# sticks-apa102-p1b.net
KiCad netlist of a schematic drawn in EAGLE
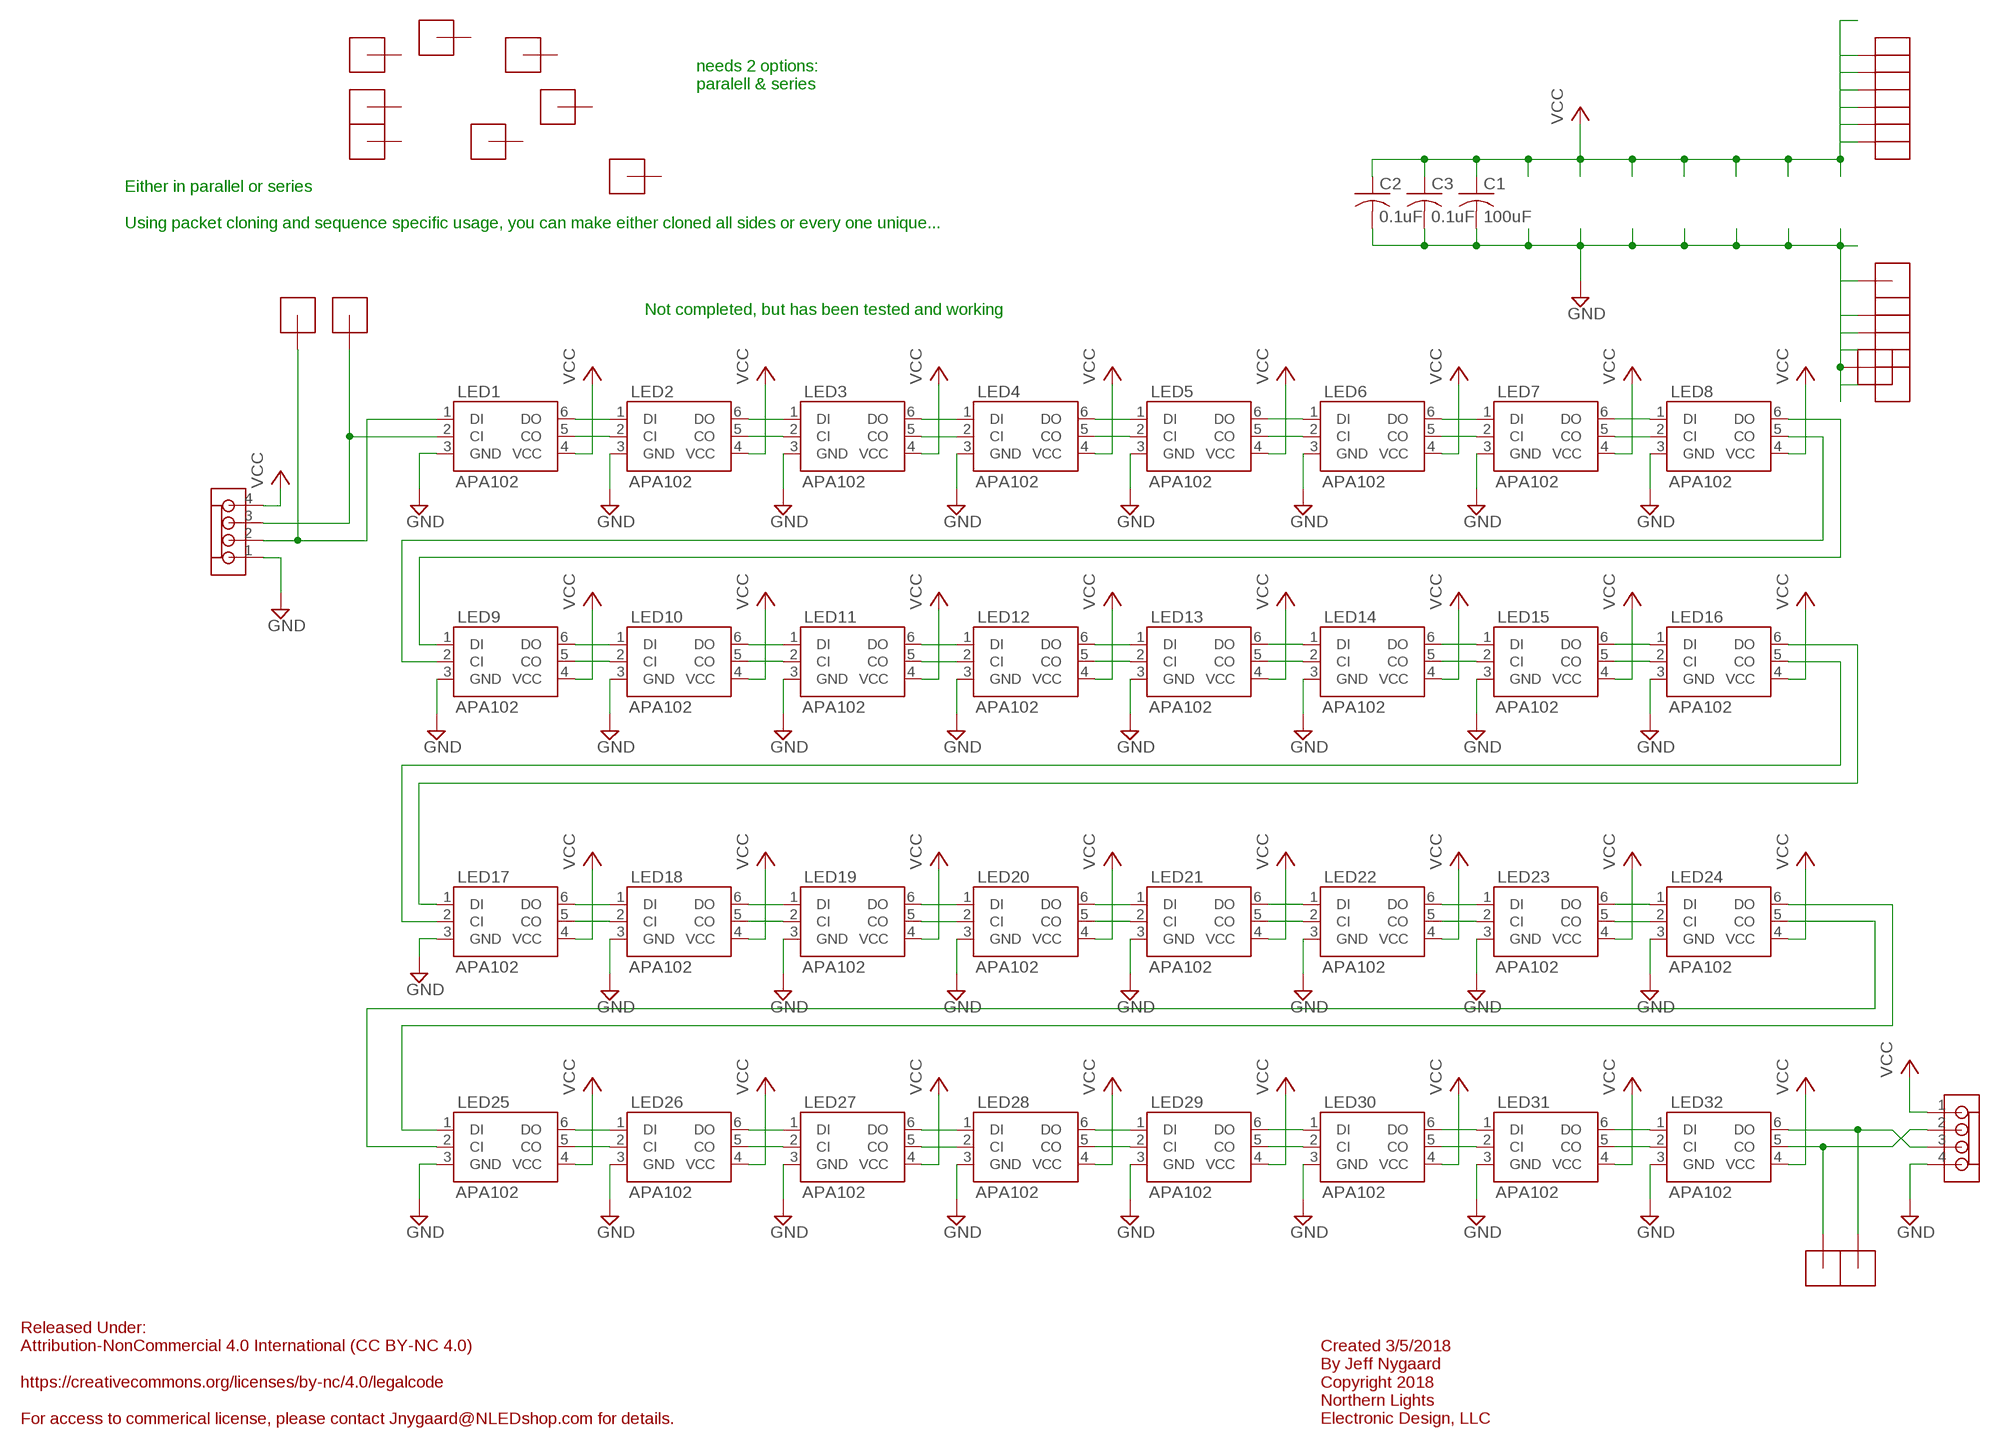
[diagram p0: schematic, sheet 1]

(export (version "E")
  (design (tool "Eeschema 10.0.6"))
  (components
    (comp (ref "C1")
      (value "100uF")
      (footprint "eagle-import:C1206")
      (libsource (lib "eagle-import") (part "C-USC1206"))
    )
    (comp (ref "C2")
      (value "0.1uF")
      (footprint "eagle-import:C1206")
      (libsource (lib "eagle-import") (part "C-USC1206"))
    )
    (comp (ref "C3")
      (value "0.1uF")
      (footprint "eagle-import:C1206")
      (libsource (lib "eagle-import") (part "C-USC1206"))
    )
    (comp (ref "CLKI")
      (value "1HEADER")
      (footprint "eagle-import:J1")
      (libsource (lib "eagle-import") (part "1HEADER"))
    )
    (comp (ref "CLKO")
      (value "1HEADER")
      (footprint "eagle-import:J1")
      (libsource (lib "eagle-import") (part "1HEADER"))
    )
    (comp (ref "DATI")
      (value "1HEADER")
      (footprint "eagle-import:J1")
      (libsource (lib "eagle-import") (part "1HEADER"))
    )
    (comp (ref "DATO")
      (value "1HEADER")
      (footprint "eagle-import:J1")
      (libsource (lib "eagle-import") (part "1HEADER"))
    )
    (comp (ref "IN")
      (value "MOLEXKK4")
      (footprint "eagle-import:MOLEXKK4")
      (libsource (lib "eagle-import") (part "MOLEXKK4"))
    )
    (comp (ref "JGND1")
      (value "1HEADER")
      (footprint "eagle-import:J1")
      (libsource (lib "eagle-import") (part "1HEADER"))
    )
    (comp (ref "JGND2")
      (value "1HEADER")
      (footprint "eagle-import:J1")
      (libsource (lib "eagle-import") (part "1HEADER"))
    )
    (comp (ref "JGND3")
      (value "1HEADER")
      (footprint "eagle-import:J1")
      (libsource (lib "eagle-import") (part "1HEADER"))
    )
    (comp (ref "JGND4")
      (value "1HEADER")
      (footprint "eagle-import:J1")
      (libsource (lib "eagle-import") (part "1HEADER"))
    )
    (comp (ref "JGND5")
      (value "1HEADER")
      (footprint "eagle-import:J1")
      (libsource (lib "eagle-import") (part "1HEADER"))
    )
    (comp (ref "JGND6")
      (value "1HEADER")
      (footprint "eagle-import:J1")
      (libsource (lib "eagle-import") (part "1HEADER"))
    )
    (comp (ref "JVCC1")
      (value "1HEADER")
      (footprint "eagle-import:J1")
      (libsource (lib "eagle-import") (part "1HEADER"))
    )
    (comp (ref "JVCC2")
      (value "1HEADER")
      (footprint "eagle-import:J1")
      (libsource (lib "eagle-import") (part "1HEADER"))
    )
    (comp (ref "JVCC3")
      (value "1HEADER")
      (footprint "eagle-import:J1")
      (libsource (lib "eagle-import") (part "1HEADER"))
    )
    (comp (ref "JVCC4")
      (value "1HEADER")
      (footprint "eagle-import:J1")
      (libsource (lib "eagle-import") (part "1HEADER"))
    )
    (comp (ref "JVCC5")
      (value "1HEADER")
      (footprint "eagle-import:J1")
      (libsource (lib "eagle-import") (part "1HEADER"))
    )
    (comp (ref "JVCC6")
      (value "1HEADER")
      (footprint "eagle-import:J1")
      (libsource (lib "eagle-import") (part "1HEADER"))
    )
    (comp (ref "LED1")
      (value "APA102")
      (footprint "eagle-import:APA102")
      (libsource (lib "eagle-import") (part "APA102"))
    )
    (comp (ref "LED2")
      (value "APA102")
      (footprint "eagle-import:APA102")
      (libsource (lib "eagle-import") (part "APA102"))
    )
    (comp (ref "LED3")
      (value "APA102")
      (footprint "eagle-import:APA102")
      (libsource (lib "eagle-import") (part "APA102"))
    )
    (comp (ref "LED4")
      (value "APA102")
      (footprint "eagle-import:APA102")
      (libsource (lib "eagle-import") (part "APA102"))
    )
    (comp (ref "LED5")
      (value "APA102")
      (footprint "eagle-import:APA102")
      (libsource (lib "eagle-import") (part "APA102"))
    )
    (comp (ref "LED6")
      (value "APA102")
      (footprint "eagle-import:APA102")
      (libsource (lib "eagle-import") (part "APA102"))
    )
    (comp (ref "LED7")
      (value "APA102")
      (footprint "eagle-import:APA102")
      (libsource (lib "eagle-import") (part "APA102"))
    )
    (comp (ref "LED8")
      (value "APA102")
      (footprint "eagle-import:APA102")
      (libsource (lib "eagle-import") (part "APA102"))
    )
    (comp (ref "LED9")
      (value "APA102")
      (footprint "eagle-import:APA102")
      (libsource (lib "eagle-import") (part "APA102"))
    )
    (comp (ref "LED10")
      (value "APA102")
      (footprint "eagle-import:APA102")
      (libsource (lib "eagle-import") (part "APA102"))
    )
    (comp (ref "LED11")
      (value "APA102")
      (footprint "eagle-import:APA102")
      (libsource (lib "eagle-import") (part "APA102"))
    )
    (comp (ref "LED12")
      (value "APA102")
      (footprint "eagle-import:APA102")
      (libsource (lib "eagle-import") (part "APA102"))
    )
    (comp (ref "LED13")
      (value "APA102")
      (footprint "eagle-import:APA102")
      (libsource (lib "eagle-import") (part "APA102"))
    )
    (comp (ref "LED14")
      (value "APA102")
      (footprint "eagle-import:APA102")
      (libsource (lib "eagle-import") (part "APA102"))
    )
    (comp (ref "LED15")
      (value "APA102")
      (footprint "eagle-import:APA102")
      (libsource (lib "eagle-import") (part "APA102"))
    )
    (comp (ref "LED16")
      (value "APA102")
      (footprint "eagle-import:APA102")
      (libsource (lib "eagle-import") (part "APA102"))
    )
    (comp (ref "LED17")
      (value "APA102")
      (footprint "eagle-import:APA102")
      (libsource (lib "eagle-import") (part "APA102"))
    )
    (comp (ref "LED18")
      (value "APA102")
      (footprint "eagle-import:APA102")
      (libsource (lib "eagle-import") (part "APA102"))
    )
    (comp (ref "LED19")
      (value "APA102")
      (footprint "eagle-import:APA102")
      (libsource (lib "eagle-import") (part "APA102"))
    )
    (comp (ref "LED20")
      (value "APA102")
      (footprint "eagle-import:APA102")
      (libsource (lib "eagle-import") (part "APA102"))
    )
    (comp (ref "LED21")
      (value "APA102")
      (footprint "eagle-import:APA102")
      (libsource (lib "eagle-import") (part "APA102"))
    )
    (comp (ref "LED22")
      (value "APA102")
      (footprint "eagle-import:APA102")
      (libsource (lib "eagle-import") (part "APA102"))
    )
    (comp (ref "LED23")
      (value "APA102")
      (footprint "eagle-import:APA102")
      (libsource (lib "eagle-import") (part "APA102"))
    )
    (comp (ref "LED24")
      (value "APA102")
      (footprint "eagle-import:APA102")
      (libsource (lib "eagle-import") (part "APA102"))
    )
    (comp (ref "LED25")
      (value "APA102")
      (footprint "eagle-import:APA102")
      (libsource (lib "eagle-import") (part "APA102"))
    )
    (comp (ref "LED26")
      (value "APA102")
      (footprint "eagle-import:APA102")
      (libsource (lib "eagle-import") (part "APA102"))
    )
    (comp (ref "LED27")
      (value "APA102")
      (footprint "eagle-import:APA102")
      (libsource (lib "eagle-import") (part "APA102"))
    )
    (comp (ref "LED28")
      (value "APA102")
      (footprint "eagle-import:APA102")
      (libsource (lib "eagle-import") (part "APA102"))
    )
    (comp (ref "LED29")
      (value "APA102")
      (footprint "eagle-import:APA102")
      (libsource (lib "eagle-import") (part "APA102"))
    )
    (comp (ref "LED30")
      (value "APA102")
      (footprint "eagle-import:APA102")
      (libsource (lib "eagle-import") (part "APA102"))
    )
    (comp (ref "LED31")
      (value "APA102")
      (footprint "eagle-import:APA102")
      (libsource (lib "eagle-import") (part "APA102"))
    )
    (comp (ref "LED32")
      (value "APA102")
      (footprint "eagle-import:APA102")
      (libsource (lib "eagle-import") (part "APA102"))
    )
    (comp (ref "M1")
      (value "1HEADER")
      (footprint "eagle-import:J1")
      (libsource (lib "eagle-import") (part "1HEADER"))
    )
    (comp (ref "M2")
      (value "1HEADER")
      (footprint "eagle-import:J1")
      (libsource (lib "eagle-import") (part "1HEADER"))
    )
    (comp (ref "M3")
      (value "1HEADER")
      (footprint "eagle-import:J1")
      (libsource (lib "eagle-import") (part "1HEADER"))
    )
    (comp (ref "M4")
      (value "1HEADER")
      (footprint "eagle-import:J1")
      (libsource (lib "eagle-import") (part "1HEADER"))
    )
    (comp (ref "M5")
      (value "1HEADER")
      (footprint "eagle-import:J1")
      (libsource (lib "eagle-import") (part "1HEADER"))
    )
    (comp (ref "M6")
      (value "1HEADER")
      (footprint "eagle-import:J1")
      (libsource (lib "eagle-import") (part "1HEADER"))
    )
    (comp (ref "M7")
      (value "1HEADER")
      (footprint "eagle-import:J1")
      (libsource (lib "eagle-import") (part "1HEADER"))
    )
    (comp (ref "M8")
      (value "1HEADER")
      (footprint "eagle-import:J1")
      (libsource (lib "eagle-import") (part "1HEADER"))
    )
    (comp (ref "OUT")
      (value "MOLEXKK4")
      (footprint "eagle-import:MOLEXKK4")
      (libsource (lib "eagle-import") (part "MOLEXKK4"))
    )
  )
  (nets
    (net (code "1") (name "GND") (class "Default")
      (node (ref "C1") (pin "2") (pinfunction "2_2") (pintype "passive"))
      (node (ref "C2") (pin "2") (pinfunction "2_2") (pintype "passive"))
      (node (ref "C3") (pin "2") (pinfunction "2_2") (pintype "passive"))
      (node (ref "IN") (pin "1") (pinfunction "1_1") (pintype "bidirectional"))
      (node (ref "JGND1") (pin "2") (pinfunction "J1_2") (pintype "bidirectional"))
      (node (ref "JGND2") (pin "2") (pinfunction "J1_2") (pintype "bidirectional"))
      (node (ref "JGND3") (pin "2") (pinfunction "J1_2") (pintype "bidirectional"))
      (node (ref "JGND4") (pin "2") (pinfunction "J1_2") (pintype "bidirectional"))
      (node (ref "JGND5") (pin "2") (pinfunction "J1_2") (pintype "bidirectional"))
      (node (ref "JGND6") (pin "2") (pinfunction "J1_2") (pintype "bidirectional"))
      (node (ref "LED1") (pin "3") (pinfunction "GND_3") (pintype "bidirectional"))
      (node (ref "LED10") (pin "3") (pinfunction "GND_3") (pintype "bidirectional"))
      (node (ref "LED11") (pin "3") (pinfunction "GND_3") (pintype "bidirectional"))
      (node (ref "LED12") (pin "3") (pinfunction "GND_3") (pintype "bidirectional"))
      (node (ref "LED13") (pin "3") (pinfunction "GND_3") (pintype "bidirectional"))
      (node (ref "LED14") (pin "3") (pinfunction "GND_3") (pintype "bidirectional"))
      (node (ref "LED15") (pin "3") (pinfunction "GND_3") (pintype "bidirectional"))
      (node (ref "LED16") (pin "3") (pinfunction "GND_3") (pintype "bidirectional"))
      (node (ref "LED17") (pin "3") (pinfunction "GND_3") (pintype "bidirectional"))
      (node (ref "LED18") (pin "3") (pinfunction "GND_3") (pintype "bidirectional"))
      (node (ref "LED19") (pin "3") (pinfunction "GND_3") (pintype "bidirectional"))
      (node (ref "LED2") (pin "3") (pinfunction "GND_3") (pintype "bidirectional"))
      (node (ref "LED20") (pin "3") (pinfunction "GND_3") (pintype "bidirectional"))
      (node (ref "LED21") (pin "3") (pinfunction "GND_3") (pintype "bidirectional"))
      (node (ref "LED22") (pin "3") (pinfunction "GND_3") (pintype "bidirectional"))
      (node (ref "LED23") (pin "3") (pinfunction "GND_3") (pintype "bidirectional"))
      (node (ref "LED24") (pin "3") (pinfunction "GND_3") (pintype "bidirectional"))
      (node (ref "LED25") (pin "3") (pinfunction "GND_3") (pintype "bidirectional"))
      (node (ref "LED26") (pin "3") (pinfunction "GND_3") (pintype "bidirectional"))
      (node (ref "LED27") (pin "3") (pinfunction "GND_3") (pintype "bidirectional"))
      (node (ref "LED28") (pin "3") (pinfunction "GND_3") (pintype "bidirectional"))
      (node (ref "LED29") (pin "3") (pinfunction "GND_3") (pintype "bidirectional"))
      (node (ref "LED3") (pin "3") (pinfunction "GND_3") (pintype "bidirectional"))
      (node (ref "LED30") (pin "3") (pinfunction "GND_3") (pintype "bidirectional"))
      (node (ref "LED31") (pin "3") (pinfunction "GND_3") (pintype "bidirectional"))
      (node (ref "LED32") (pin "3") (pinfunction "GND_3") (pintype "bidirectional"))
      (node (ref "LED4") (pin "3") (pinfunction "GND_3") (pintype "bidirectional"))
      (node (ref "LED5") (pin "3") (pinfunction "GND_3") (pintype "bidirectional"))
      (node (ref "LED6") (pin "3") (pinfunction "GND_3") (pintype "bidirectional"))
      (node (ref "LED7") (pin "3") (pinfunction "GND_3") (pintype "bidirectional"))
      (node (ref "LED8") (pin "3") (pinfunction "GND_3") (pintype "bidirectional"))
      (node (ref "LED9") (pin "3") (pinfunction "GND_3") (pintype "bidirectional"))
      (node (ref "OUT") (pin "4") (pinfunction "4_4") (pintype "bidirectional"))
    )
    (net (code "2") (name "Net-(CLKI-J1)") (class "Default")
      (node (ref "CLKI") (pin "2") (pinfunction "J1_2") (pintype "bidirectional"))
      (node (ref "IN") (pin "3") (pinfunction "3_3") (pintype "bidirectional"))
      (node (ref "LED1") (pin "2") (pinfunction "CI_2") (pintype "bidirectional"))
    )
    (net (code "3") (name "Net-(CLKO-J1)") (class "Default")
      (node (ref "CLKO") (pin "2") (pinfunction "J1_2") (pintype "bidirectional"))
      (node (ref "LED32") (pin "5") (pinfunction "CO_5") (pintype "bidirectional"))
      (node (ref "OUT") (pin "2") (pinfunction "2_2") (pintype "bidirectional"))
    )
    (net (code "4") (name "Net-(DATI-J1)") (class "Default")
      (node (ref "DATI") (pin "2") (pinfunction "J1_2") (pintype "bidirectional"))
      (node (ref "IN") (pin "2") (pinfunction "2_2") (pintype "bidirectional"))
      (node (ref "LED1") (pin "1") (pinfunction "DI_1") (pintype "bidirectional"))
    )
    (net (code "5") (name "Net-(DATO-J1)") (class "Default")
      (node (ref "DATO") (pin "2") (pinfunction "J1_2") (pintype "bidirectional"))
      (node (ref "LED32") (pin "6") (pinfunction "DO_6") (pintype "bidirectional"))
      (node (ref "OUT") (pin "3") (pinfunction "3_3") (pintype "bidirectional"))
    )
    (net (code "6") (name "Net-(LED1-CO)") (class "Default")
      (node (ref "LED1") (pin "5") (pinfunction "CO_5") (pintype "bidirectional"))
      (node (ref "LED2") (pin "2") (pinfunction "CI_2") (pintype "bidirectional"))
    )
    (net (code "7") (name "Net-(LED1-DO)") (class "Default")
      (node (ref "LED1") (pin "6") (pinfunction "DO_6") (pintype "bidirectional"))
      (node (ref "LED2") (pin "1") (pinfunction "DI_1") (pintype "bidirectional"))
    )
    (net (code "8") (name "Net-(LED2-CO)") (class "Default")
      (node (ref "LED2") (pin "5") (pinfunction "CO_5") (pintype "bidirectional"))
      (node (ref "LED3") (pin "2") (pinfunction "CI_2") (pintype "bidirectional"))
    )
    (net (code "9") (name "Net-(LED2-DO)") (class "Default")
      (node (ref "LED2") (pin "6") (pinfunction "DO_6") (pintype "bidirectional"))
      (node (ref "LED3") (pin "1") (pinfunction "DI_1") (pintype "bidirectional"))
    )
    (net (code "10") (name "Net-(LED3-CO)") (class "Default")
      (node (ref "LED3") (pin "5") (pinfunction "CO_5") (pintype "bidirectional"))
      (node (ref "LED4") (pin "2") (pinfunction "CI_2") (pintype "bidirectional"))
    )
    (net (code "11") (name "Net-(LED3-DO)") (class "Default")
      (node (ref "LED3") (pin "6") (pinfunction "DO_6") (pintype "bidirectional"))
      (node (ref "LED4") (pin "1") (pinfunction "DI_1") (pintype "bidirectional"))
    )
    (net (code "12") (name "Net-(LED4-CO)") (class "Default")
      (node (ref "LED4") (pin "5") (pinfunction "CO_5") (pintype "bidirectional"))
      (node (ref "LED5") (pin "2") (pinfunction "CI_2") (pintype "bidirectional"))
    )
    (net (code "13") (name "Net-(LED4-DO)") (class "Default")
      (node (ref "LED4") (pin "6") (pinfunction "DO_6") (pintype "bidirectional"))
      (node (ref "LED5") (pin "1") (pinfunction "DI_1") (pintype "bidirectional"))
    )
    (net (code "14") (name "Net-(LED5-CO)") (class "Default")
      (node (ref "LED5") (pin "5") (pinfunction "CO_5") (pintype "bidirectional"))
      (node (ref "LED6") (pin "2") (pinfunction "CI_2") (pintype "bidirectional"))
    )
    (net (code "15") (name "Net-(LED5-DO)") (class "Default")
      (node (ref "LED5") (pin "6") (pinfunction "DO_6") (pintype "bidirectional"))
      (node (ref "LED6") (pin "1") (pinfunction "DI_1") (pintype "bidirectional"))
    )
    (net (code "16") (name "Net-(LED6-CO)") (class "Default")
      (node (ref "LED6") (pin "5") (pinfunction "CO_5") (pintype "bidirectional"))
      (node (ref "LED7") (pin "2") (pinfunction "CI_2") (pintype "bidirectional"))
    )
    (net (code "17") (name "Net-(LED6-DO)") (class "Default")
      (node (ref "LED6") (pin "6") (pinfunction "DO_6") (pintype "bidirectional"))
      (node (ref "LED7") (pin "1") (pinfunction "DI_1") (pintype "bidirectional"))
    )
    (net (code "18") (name "Net-(LED7-CO)") (class "Default")
      (node (ref "LED7") (pin "5") (pinfunction "CO_5") (pintype "bidirectional"))
      (node (ref "LED8") (pin "2") (pinfunction "CI_2") (pintype "bidirectional"))
    )
    (net (code "19") (name "Net-(LED7-DO)") (class "Default")
      (node (ref "LED7") (pin "6") (pinfunction "DO_6") (pintype "bidirectional"))
      (node (ref "LED8") (pin "1") (pinfunction "DI_1") (pintype "bidirectional"))
    )
    (net (code "20") (name "Net-(LED8-CO)") (class "Default")
      (node (ref "LED8") (pin "5") (pinfunction "CO_5") (pintype "bidirectional"))
      (node (ref "LED9") (pin "2") (pinfunction "CI_2") (pintype "bidirectional"))
    )
    (net (code "21") (name "Net-(LED8-DO)") (class "Default")
      (node (ref "LED8") (pin "6") (pinfunction "DO_6") (pintype "bidirectional"))
      (node (ref "LED9") (pin "1") (pinfunction "DI_1") (pintype "bidirectional"))
    )
    (net (code "22") (name "Net-(LED10-CI)") (class "Default")
      (node (ref "LED10") (pin "2") (pinfunction "CI_2") (pintype "bidirectional"))
      (node (ref "LED9") (pin "5") (pinfunction "CO_5") (pintype "bidirectional"))
    )
    (net (code "23") (name "Net-(LED10-CO)") (class "Default")
      (node (ref "LED10") (pin "5") (pinfunction "CO_5") (pintype "bidirectional"))
      (node (ref "LED11") (pin "2") (pinfunction "CI_2") (pintype "bidirectional"))
    )
    (net (code "24") (name "Net-(LED10-DI)") (class "Default")
      (node (ref "LED10") (pin "1") (pinfunction "DI_1") (pintype "bidirectional"))
      (node (ref "LED9") (pin "6") (pinfunction "DO_6") (pintype "bidirectional"))
    )
    (net (code "25") (name "Net-(LED10-DO)") (class "Default")
      (node (ref "LED10") (pin "6") (pinfunction "DO_6") (pintype "bidirectional"))
      (node (ref "LED11") (pin "1") (pinfunction "DI_1") (pintype "bidirectional"))
    )
    (net (code "26") (name "Net-(LED11-CO)") (class "Default")
      (node (ref "LED11") (pin "5") (pinfunction "CO_5") (pintype "bidirectional"))
      (node (ref "LED12") (pin "2") (pinfunction "CI_2") (pintype "bidirectional"))
    )
    (net (code "27") (name "Net-(LED11-DO)") (class "Default")
      (node (ref "LED11") (pin "6") (pinfunction "DO_6") (pintype "bidirectional"))
      (node (ref "LED12") (pin "1") (pinfunction "DI_1") (pintype "bidirectional"))
    )
    (net (code "28") (name "Net-(LED12-CO)") (class "Default")
      (node (ref "LED12") (pin "5") (pinfunction "CO_5") (pintype "bidirectional"))
      (node (ref "LED13") (pin "2") (pinfunction "CI_2") (pintype "bidirectional"))
    )
    (net (code "29") (name "Net-(LED12-DO)") (class "Default")
      (node (ref "LED12") (pin "6") (pinfunction "DO_6") (pintype "bidirectional"))
      (node (ref "LED13") (pin "1") (pinfunction "DI_1") (pintype "bidirectional"))
    )
    (net (code "30") (name "Net-(LED13-CO)") (class "Default")
      (node (ref "LED13") (pin "5") (pinfunction "CO_5") (pintype "bidirectional"))
      (node (ref "LED14") (pin "2") (pinfunction "CI_2") (pintype "bidirectional"))
    )
    (net (code "31") (name "Net-(LED13-DO)") (class "Default")
      (node (ref "LED13") (pin "6") (pinfunction "DO_6") (pintype "bidirectional"))
      (node (ref "LED14") (pin "1") (pinfunction "DI_1") (pintype "bidirectional"))
    )
    (net (code "32") (name "Net-(LED14-CO)") (class "Default")
      (node (ref "LED14") (pin "5") (pinfunction "CO_5") (pintype "bidirectional"))
      (node (ref "LED15") (pin "2") (pinfunction "CI_2") (pintype "bidirectional"))
    )
    (net (code "33") (name "Net-(LED14-DO)") (class "Default")
      (node (ref "LED14") (pin "6") (pinfunction "DO_6") (pintype "bidirectional"))
      (node (ref "LED15") (pin "1") (pinfunction "DI_1") (pintype "bidirectional"))
    )
    (net (code "34") (name "Net-(LED15-CO)") (class "Default")
      (node (ref "LED15") (pin "5") (pinfunction "CO_5") (pintype "bidirectional"))
      (node (ref "LED16") (pin "2") (pinfunction "CI_2") (pintype "bidirectional"))
    )
    (net (code "35") (name "Net-(LED15-DO)") (class "Default")
      (node (ref "LED15") (pin "6") (pinfunction "DO_6") (pintype "bidirectional"))
      (node (ref "LED16") (pin "1") (pinfunction "DI_1") (pintype "bidirectional"))
    )
    (net (code "36") (name "Net-(LED16-CO)") (class "Default")
      (node (ref "LED16") (pin "5") (pinfunction "CO_5") (pintype "bidirectional"))
      (node (ref "LED17") (pin "2") (pinfunction "CI_2") (pintype "bidirectional"))
    )
    (net (code "37") (name "Net-(LED16-DO)") (class "Default")
      (node (ref "LED16") (pin "6") (pinfunction "DO_6") (pintype "bidirectional"))
      (node (ref "LED17") (pin "1") (pinfunction "DI_1") (pintype "bidirectional"))
    )
    (net (code "38") (name "Net-(LED17-CO)") (class "Default")
      (node (ref "LED17") (pin "5") (pinfunction "CO_5") (pintype "bidirectional"))
      (node (ref "LED18") (pin "2") (pinfunction "CI_2") (pintype "bidirectional"))
    )
    (net (code "39") (name "Net-(LED17-DO)") (class "Default")
      (node (ref "LED17") (pin "6") (pinfunction "DO_6") (pintype "bidirectional"))
      (node (ref "LED18") (pin "1") (pinfunction "DI_1") (pintype "bidirectional"))
    )
    (net (code "40") (name "Net-(LED18-CO)") (class "Default")
      (node (ref "LED18") (pin "5") (pinfunction "CO_5") (pintype "bidirectional"))
      (node (ref "LED19") (pin "2") (pinfunction "CI_2") (pintype "bidirectional"))
    )
    (net (code "41") (name "Net-(LED18-DO)") (class "Default")
      (node (ref "LED18") (pin "6") (pinfunction "DO_6") (pintype "bidirectional"))
      (node (ref "LED19") (pin "1") (pinfunction "DI_1") (pintype "bidirectional"))
    )
    (net (code "42") (name "Net-(LED19-CO)") (class "Default")
      (node (ref "LED19") (pin "5") (pinfunction "CO_5") (pintype "bidirectional"))
      (node (ref "LED20") (pin "2") (pinfunction "CI_2") (pintype "bidirectional"))
    )
    (net (code "43") (name "Net-(LED19-DO)") (class "Default")
      (node (ref "LED19") (pin "6") (pinfunction "DO_6") (pintype "bidirectional"))
      (node (ref "LED20") (pin "1") (pinfunction "DI_1") (pintype "bidirectional"))
    )
    (net (code "44") (name "Net-(LED20-CO)") (class "Default")
      (node (ref "LED20") (pin "5") (pinfunction "CO_5") (pintype "bidirectional"))
      (node (ref "LED21") (pin "2") (pinfunction "CI_2") (pintype "bidirectional"))
    )
    (net (code "45") (name "Net-(LED20-DO)") (class "Default")
      (node (ref "LED20") (pin "6") (pinfunction "DO_6") (pintype "bidirectional"))
      (node (ref "LED21") (pin "1") (pinfunction "DI_1") (pintype "bidirectional"))
    )
    (net (code "46") (name "Net-(LED21-CO)") (class "Default")
      (node (ref "LED21") (pin "5") (pinfunction "CO_5") (pintype "bidirectional"))
      (node (ref "LED22") (pin "2") (pinfunction "CI_2") (pintype "bidirectional"))
    )
    (net (code "47") (name "Net-(LED21-DO)") (class "Default")
      (node (ref "LED21") (pin "6") (pinfunction "DO_6") (pintype "bidirectional"))
      (node (ref "LED22") (pin "1") (pinfunction "DI_1") (pintype "bidirectional"))
    )
    (net (code "48") (name "Net-(LED22-CO)") (class "Default")
      (node (ref "LED22") (pin "5") (pinfunction "CO_5") (pintype "bidirectional"))
      (node (ref "LED23") (pin "2") (pinfunction "CI_2") (pintype "bidirectional"))
    )
    (net (code "49") (name "Net-(LED22-DO)") (class "Default")
      (node (ref "LED22") (pin "6") (pinfunction "DO_6") (pintype "bidirectional"))
      (node (ref "LED23") (pin "1") (pinfunction "DI_1") (pintype "bidirectional"))
    )
    (net (code "50") (name "Net-(LED23-CO)") (class "Default")
      (node (ref "LED23") (pin "5") (pinfunction "CO_5") (pintype "bidirectional"))
      (node (ref "LED24") (pin "2") (pinfunction "CI_2") (pintype "bidirectional"))
    )
    (net (code "51") (name "Net-(LED23-DO)") (class "Default")
      (node (ref "LED23") (pin "6") (pinfunction "DO_6") (pintype "bidirectional"))
      (node (ref "LED24") (pin "1") (pinfunction "DI_1") (pintype "bidirectional"))
    )
    (net (code "52") (name "Net-(LED24-CO)") (class "Default")
      (node (ref "LED24") (pin "5") (pinfunction "CO_5") (pintype "bidirectional"))
      (node (ref "LED25") (pin "2") (pinfunction "CI_2") (pintype "bidirectional"))
    )
    (net (code "53") (name "Net-(LED24-DO)") (class "Default")
      (node (ref "LED24") (pin "6") (pinfunction "DO_6") (pintype "bidirectional"))
      (node (ref "LED25") (pin "1") (pinfunction "DI_1") (pintype "bidirectional"))
    )
    (net (code "54") (name "Net-(LED25-CO)") (class "Default")
      (node (ref "LED25") (pin "5") (pinfunction "CO_5") (pintype "bidirectional"))
      (node (ref "LED26") (pin "2") (pinfunction "CI_2") (pintype "bidirectional"))
    )
    (net (code "55") (name "Net-(LED25-DO)") (class "Default")
      (node (ref "LED25") (pin "6") (pinfunction "DO_6") (pintype "bidirectional"))
      (node (ref "LED26") (pin "1") (pinfunction "DI_1") (pintype "bidirectional"))
    )
    (net (code "56") (name "Net-(LED26-CO)") (class "Default")
      (node (ref "LED26") (pin "5") (pinfunction "CO_5") (pintype "bidirectional"))
      (node (ref "LED27") (pin "2") (pinfunction "CI_2") (pintype "bidirectional"))
    )
    (net (code "57") (name "Net-(LED26-DO)") (class "Default")
      (node (ref "LED26") (pin "6") (pinfunction "DO_6") (pintype "bidirectional"))
      (node (ref "LED27") (pin "1") (pinfunction "DI_1") (pintype "bidirectional"))
    )
    (net (code "58") (name "Net-(LED27-CO)") (class "Default")
      (node (ref "LED27") (pin "5") (pinfunction "CO_5") (pintype "bidirectional"))
      (node (ref "LED28") (pin "2") (pinfunction "CI_2") (pintype "bidirectional"))
    )
    (net (code "59") (name "Net-(LED27-DO)") (class "Default")
      (node (ref "LED27") (pin "6") (pinfunction "DO_6") (pintype "bidirectional"))
      (node (ref "LED28") (pin "1") (pinfunction "DI_1") (pintype "bidirectional"))
    )
    (net (code "60") (name "Net-(LED28-CO)") (class "Default")
      (node (ref "LED28") (pin "5") (pinfunction "CO_5") (pintype "bidirectional"))
      (node (ref "LED29") (pin "2") (pinfunction "CI_2") (pintype "bidirectional"))
    )
    (net (code "61") (name "Net-(LED28-DO)") (class "Default")
      (node (ref "LED28") (pin "6") (pinfunction "DO_6") (pintype "bidirectional"))
      (node (ref "LED29") (pin "1") (pinfunction "DI_1") (pintype "bidirectional"))
    )
    (net (code "62") (name "Net-(LED29-CO)") (class "Default")
      (node (ref "LED29") (pin "5") (pinfunction "CO_5") (pintype "bidirectional"))
      (node (ref "LED30") (pin "2") (pinfunction "CI_2") (pintype "bidirectional"))
    )
    (net (code "63") (name "Net-(LED29-DO)") (class "Default")
      (node (ref "LED29") (pin "6") (pinfunction "DO_6") (pintype "bidirectional"))
      (node (ref "LED30") (pin "1") (pinfunction "DI_1") (pintype "bidirectional"))
    )
    (net (code "64") (name "Net-(LED30-CO)") (class "Default")
      (node (ref "LED30") (pin "5") (pinfunction "CO_5") (pintype "bidirectional"))
      (node (ref "LED31") (pin "2") (pinfunction "CI_2") (pintype "bidirectional"))
    )
    (net (code "65") (name "Net-(LED30-DO)") (class "Default")
      (node (ref "LED30") (pin "6") (pinfunction "DO_6") (pintype "bidirectional"))
      (node (ref "LED31") (pin "1") (pinfunction "DI_1") (pintype "bidirectional"))
    )
    (net (code "66") (name "Net-(LED31-CO)") (class "Default")
      (node (ref "LED31") (pin "5") (pinfunction "CO_5") (pintype "bidirectional"))
      (node (ref "LED32") (pin "2") (pinfunction "CI_2") (pintype "bidirectional"))
    )
    (net (code "67") (name "Net-(LED31-DO)") (class "Default")
      (node (ref "LED31") (pin "6") (pinfunction "DO_6") (pintype "bidirectional"))
      (node (ref "LED32") (pin "1") (pinfunction "DI_1") (pintype "bidirectional"))
    )
    (net (code "68") (name "VCC") (class "Default")
      (node (ref "C1") (pin "1") (pinfunction "1_1") (pintype "passive"))
      (node (ref "C2") (pin "1") (pinfunction "1_1") (pintype "passive"))
      (node (ref "C3") (pin "1") (pinfunction "1_1") (pintype "passive"))
      (node (ref "IN") (pin "4") (pinfunction "4_4") (pintype "bidirectional"))
      (node (ref "JVCC1") (pin "2") (pinfunction "J1_2") (pintype "bidirectional"))
      (node (ref "JVCC2") (pin "2") (pinfunction "J1_2") (pintype "bidirectional"))
      (node (ref "JVCC3") (pin "2") (pinfunction "J1_2") (pintype "bidirectional"))
      (node (ref "JVCC4") (pin "2") (pinfunction "J1_2") (pintype "bidirectional"))
      (node (ref "JVCC5") (pin "2") (pinfunction "J1_2") (pintype "bidirectional"))
      (node (ref "JVCC6") (pin "2") (pinfunction "J1_2") (pintype "bidirectional"))
      (node (ref "LED1") (pin "4") (pinfunction "VCC_4") (pintype "bidirectional"))
      (node (ref "LED10") (pin "4") (pinfunction "VCC_4") (pintype "bidirectional"))
      (node (ref "LED11") (pin "4") (pinfunction "VCC_4") (pintype "bidirectional"))
      (node (ref "LED12") (pin "4") (pinfunction "VCC_4") (pintype "bidirectional"))
      (node (ref "LED13") (pin "4") (pinfunction "VCC_4") (pintype "bidirectional"))
      (node (ref "LED14") (pin "4") (pinfunction "VCC_4") (pintype "bidirectional"))
      (node (ref "LED15") (pin "4") (pinfunction "VCC_4") (pintype "bidirectional"))
      (node (ref "LED16") (pin "4") (pinfunction "VCC_4") (pintype "bidirectional"))
      (node (ref "LED17") (pin "4") (pinfunction "VCC_4") (pintype "bidirectional"))
      (node (ref "LED18") (pin "4") (pinfunction "VCC_4") (pintype "bidirectional"))
      (node (ref "LED19") (pin "4") (pinfunction "VCC_4") (pintype "bidirectional"))
      (node (ref "LED2") (pin "4") (pinfunction "VCC_4") (pintype "bidirectional"))
      (node (ref "LED20") (pin "4") (pinfunction "VCC_4") (pintype "bidirectional"))
      (node (ref "LED21") (pin "4") (pinfunction "VCC_4") (pintype "bidirectional"))
      (node (ref "LED22") (pin "4") (pinfunction "VCC_4") (pintype "bidirectional"))
      (node (ref "LED23") (pin "4") (pinfunction "VCC_4") (pintype "bidirectional"))
      (node (ref "LED24") (pin "4") (pinfunction "VCC_4") (pintype "bidirectional"))
      (node (ref "LED25") (pin "4") (pinfunction "VCC_4") (pintype "bidirectional"))
      (node (ref "LED26") (pin "4") (pinfunction "VCC_4") (pintype "bidirectional"))
      (node (ref "LED27") (pin "4") (pinfunction "VCC_4") (pintype "bidirectional"))
      (node (ref "LED28") (pin "4") (pinfunction "VCC_4") (pintype "bidirectional"))
      (node (ref "LED29") (pin "4") (pinfunction "VCC_4") (pintype "bidirectional"))
      (node (ref "LED3") (pin "4") (pinfunction "VCC_4") (pintype "bidirectional"))
      (node (ref "LED30") (pin "4") (pinfunction "VCC_4") (pintype "bidirectional"))
      (node (ref "LED31") (pin "4") (pinfunction "VCC_4") (pintype "bidirectional"))
      (node (ref "LED32") (pin "4") (pinfunction "VCC_4") (pintype "bidirectional"))
      (node (ref "LED4") (pin "4") (pinfunction "VCC_4") (pintype "bidirectional"))
      (node (ref "LED5") (pin "4") (pinfunction "VCC_4") (pintype "bidirectional"))
      (node (ref "LED6") (pin "4") (pinfunction "VCC_4") (pintype "bidirectional"))
      (node (ref "LED7") (pin "4") (pinfunction "VCC_4") (pintype "bidirectional"))
      (node (ref "LED8") (pin "4") (pinfunction "VCC_4") (pintype "bidirectional"))
      (node (ref "LED9") (pin "4") (pinfunction "VCC_4") (pintype "bidirectional"))
      (node (ref "OUT") (pin "1") (pinfunction "1_1") (pintype "bidirectional"))
    )
    (net (code "69") (name "unconnected-(M1-J1-Pad2)") (class "Default")
      (node (ref "M1") (pin "2") (pinfunction "J1_2") (pintype "bidirectional"))
    )
    (net (code "70") (name "unconnected-(M2-J1-Pad2)") (class "Default")
      (node (ref "M2") (pin "2") (pinfunction "J1_2") (pintype "bidirectional"))
    )
    (net (code "71") (name "unconnected-(M3-J1-Pad2)") (class "Default")
      (node (ref "M3") (pin "2") (pinfunction "J1_2") (pintype "bidirectional"))
    )
    (net (code "72") (name "unconnected-(M4-J1-Pad2)") (class "Default")
      (node (ref "M4") (pin "2") (pinfunction "J1_2") (pintype "bidirectional"))
    )
    (net (code "73") (name "unconnected-(M5-J1-Pad2)") (class "Default")
      (node (ref "M5") (pin "2") (pinfunction "J1_2") (pintype "bidirectional"))
    )
    (net (code "74") (name "unconnected-(M6-J1-Pad2)") (class "Default")
      (node (ref "M6") (pin "2") (pinfunction "J1_2") (pintype "bidirectional"))
    )
    (net (code "75") (name "unconnected-(M7-J1-Pad2)") (class "Default")
      (node (ref "M7") (pin "2") (pinfunction "J1_2") (pintype "bidirectional"))
    )
    (net (code "76") (name "unconnected-(M8-J1-Pad2)") (class "Default")
      (node (ref "M8") (pin "2") (pinfunction "J1_2") (pintype "bidirectional"))
    )
  )
)
